# Microcontroller_circuit.net
KiCad netlist of a schematic drawn in Altium Designer
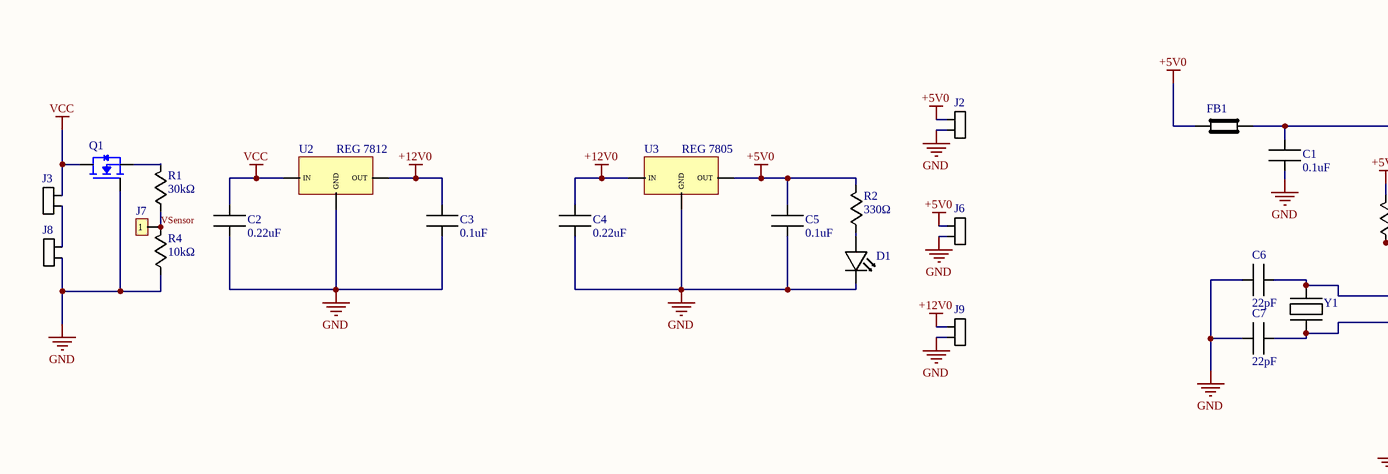
[diagram p0: Microcontroller circuit.SchDoc, left]
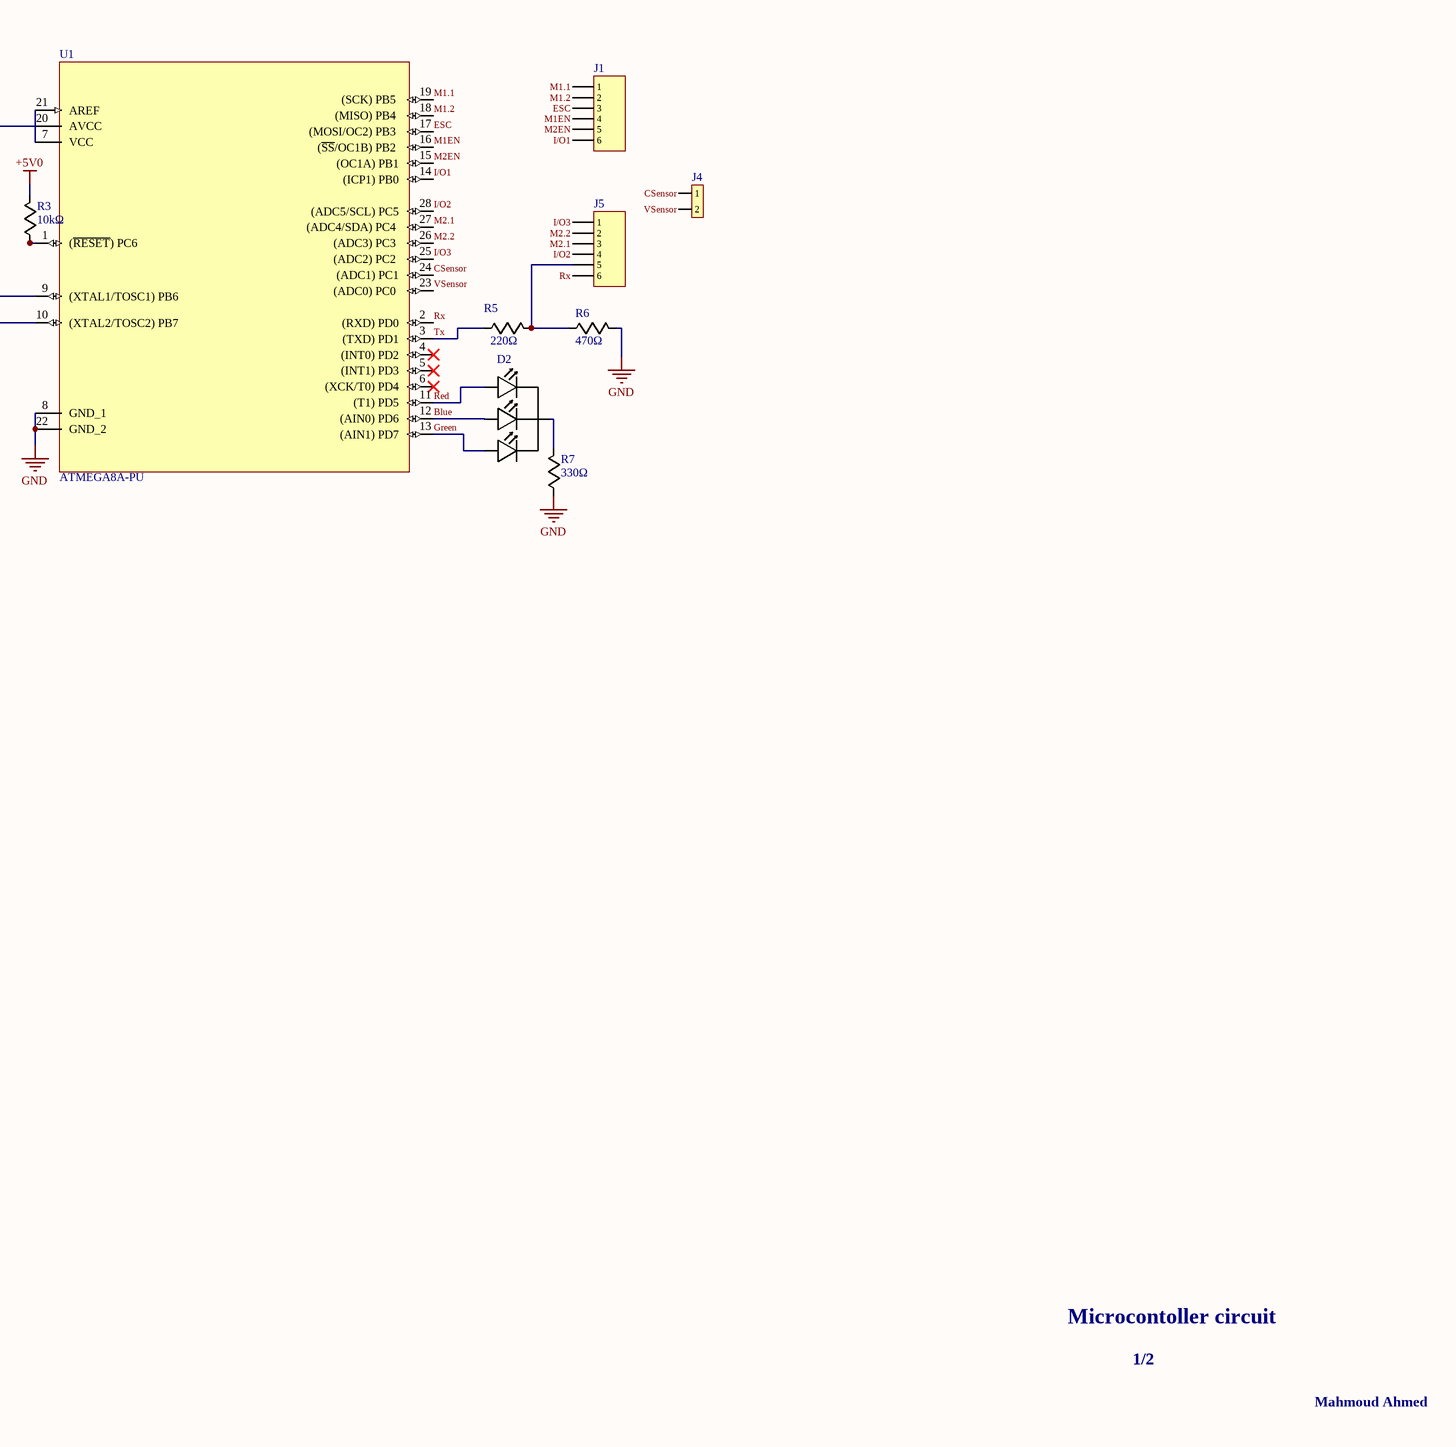
[diagram p1: Microcontroller circuit.SchDoc, right]

(export (version "E")
  (design (tool "Eeschema 10.0.6"))
  (components
    (comp (ref "C1")
      (value "0.1uF")
      (footprint "C0805")
      (description "CAP CER 0.1UF 50V X7R 0805")
      (fields (field (name "MANUFACTURER") "TDK Corporation") (field (name "MPN") "C2012X7R1H104K085AA"))
      (libsource (lib "Microcontroller circuit") (part "0.1uF CAP"))
    )
    (comp (ref "C2")
      (value "0.22uF")
      (footprint "C0805")
      (description "CAP CER 0.22UF 25V X7R 0805")
      (fields (field (name "MPN") "CC0805KRX7R8BB224") (field (name "MANUFACTURER") "YAGEO"))
      (libsource (lib "Microcontroller circuit") (part "0.22uF CAP"))
    )
    (comp (ref "C3")
      (value "0.1uF")
      (footprint "C0805")
      (description "CAP CER 0.1UF 50V X7R 0805")
      (fields (field (name "MANUFACTURER") "TDK Corporation") (field (name "MPN") "C2012X7R1H104K085AA"))
      (libsource (lib "Microcontroller circuit") (part "0.1uF CAP"))
    )
    (comp (ref "C4")
      (value "0.22uF")
      (footprint "C0805")
      (description "CAP CER 0.22UF 25V X7R 0805")
      (fields (field (name "MPN") "CC0805KRX7R8BB224") (field (name "MANUFACTURER") "YAGEO"))
      (libsource (lib "Microcontroller circuit") (part "0.22uF CAP"))
    )
    (comp (ref "C5")
      (value "0.1uF")
      (footprint "C0805")
      (description "CAP CER 0.1UF 50V X7R 0805")
      (fields (field (name "MANUFACTURER") "TDK Corporation") (field (name "MPN") "C2012X7R1H104K085AA"))
      (libsource (lib "Microcontroller circuit") (part "0.1uF CAP"))
    )
    (comp (ref "C6")
      (value "22pF")
      (footprint "C0805")
      (description "CAP THIN FILM 22PF 50V 0805")
      (fields (field (name "MPN") "08055J220FBTTR") (field (name "MANUFACTURER") "KYOCERA AVX"))
      (libsource (lib "Microcontroller circuit") (part "22pF CAP"))
    )
    (comp (ref "C7")
      (value "22pF")
      (footprint "C0805")
      (description "CAP THIN FILM 22PF 50V 0805")
      (fields (field (name "MPN") "08055J220FBTTR") (field (name "MANUFACTURER") "KYOCERA AVX"))
      (libsource (lib "Microcontroller circuit") (part "22pF CAP"))
    )
    (comp (ref "D1")
      (value "RedLED")
      (footprint "THT_LED")
      (description "LED RED CLEAR T-1 T/H")
      (fields (field (name "MPN") "WP132XIT") (field (name "MANUFACTURER") "Kingbright"))
      (libsource (lib "Microcontroller circuit") (part "WP132XIT"))
    )
    (comp (ref "D2")
      (value "WP154A4SUREQBFZGC")
      (footprint "RGB LED")
      (description "LED RGB CLEAR T-1 3/4 T/H")
      (fields (field (name "MANUFACTURER") "Kingbright"))
      (libsource (lib "Microcontroller circuit") (part "RGB LED"))
    )
    (comp (ref "FB1")
      (value "BKP2125HS101-T")
      (footprint "FB0805")
      (description "FERRITE BEAD 100 OHM 0805 1LN")
      (fields (field (name "MANUFACTURER") "Taiyo Yuden"))
      (libsource (lib "Microcontroller circuit") (part "Ferrite Bead"))
    )
    (comp (ref "J1")
      (value "M20-7820646")
      (footprint "HDR 1x6F")
      (description "CONN RCPT 6POS 0.1 TIN PCB")
      (fields (field (name "MANUFACTURER") "Harwin Inc."))
      (libsource (lib "Microcontroller circuit") (part "HDR 1x6F"))
    )
    (comp (ref "J2")
      (value "102-6179-ND")
      (footprint "Terminal block")
      (description "TERMINAL BLOCK, SCREW TYPE, 5.08")
      (fields (field (name "MPN") "TB004-508-02BE") (field (name "MANUFACTURER") "CUI Devices"))
      (libsource (lib "Microcontroller circuit") (part "Terminal block"))
    )
    (comp (ref "J3")
      (value "102-6179-ND")
      (footprint "Terminal block")
      (description "TERMINAL BLOCK, SCREW TYPE, 5.08")
      (fields (field (name "MPN") "TB004-508-02BE") (field (name "MANUFACTURER") "CUI Devices"))
      (libsource (lib "Microcontroller circuit") (part "Terminal block"))
    )
    (comp (ref "J4")
      (value "68000-202HLF")
      (footprint "HDR 1x2M")
      (description "CONN HEADER VERT 2POS 2.54MM")
      (fields (field (name "MANUFACTURER") "Amphenol ICC (FCI)"))
      (libsource (lib "Microcontroller circuit") (part "HDR 1x2M"))
    )
    (comp (ref "J5")
      (value "M20-7820646")
      (footprint "HDR 1x6F")
      (description "CONN RCPT 6POS 0.1 TIN PCB")
      (fields (field (name "MANUFACTURER") "Harwin Inc."))
      (libsource (lib "Microcontroller circuit") (part "HDR 1x6F"))
    )
    (comp (ref "J6")
      (value "102-6179-ND")
      (footprint "Terminal block")
      (description "TERMINAL BLOCK, SCREW TYPE, 5.08")
      (fields (field (name "MPN") "TB004-508-02BE") (field (name "MANUFACTURER") "CUI Devices"))
      (libsource (lib "Microcontroller circuit") (part "Terminal block"))
    )
    (comp (ref "J7")
      (value "PH1-01-UA")
      (footprint "HDR 1x1M")
      (description "CONN HEADER VERT 1POS 2.54MM")
      (fields (field (name "MANUFACTURER") "Adam Tech"))
      (libsource (lib "Microcontroller circuit") (part "HDR 1x1M"))
    )
    (comp (ref "J8")
      (value "102-6179-ND")
      (footprint "Terminal block")
      (description "TERMINAL BLOCK, SCREW TYPE, 5.08")
      (fields (field (name "MPN") "TB004-508-02BE") (field (name "MANUFACTURER") "CUI Devices"))
      (libsource (lib "Microcontroller circuit") (part "Terminal block"))
    )
    (comp (ref "J9")
      (value "102-6179-ND")
      (footprint "Terminal block")
      (description "TERMINAL BLOCK, SCREW TYPE, 5.08")
      (fields (field (name "MPN") "TB004-508-02BE") (field (name "MANUFACTURER") "CUI Devices"))
      (libsource (lib "Microcontroller circuit") (part "Terminal block"))
    )
    (comp (ref "Q1")
      (value "IRF9530NPBF")
      (footprint "IRF9530NPBF")
      (description "MOSFET P-CH 100V 14A TO220AB")
      (fields (field (name "MANUFACTURER") "Infineon Technologies"))
      (libsource (lib "Microcontroller circuit") (part "IRF9530NPBF"))
    )
    (comp (ref "R1")
      (value "30kΩ")
      (footprint "R0805")
      (description "RES 330 OHM 1% 1/8W 0805")
      (fields (field (name "MPN") "RC0805FR-07330RL") (field (name "MANUFACTURER") "YAGEO"))
      (libsource (lib "Microcontroller circuit") (part "330Ω RES"))
    )
    (comp (ref "R2")
      (value "330Ω")
      (footprint "R0805")
      (description "RES 330 OHM 1% 1/8W 0805")
      (fields (field (name "MPN") "RC0805FR-07330RL") (field (name "MANUFACTURER") "YAGEO"))
      (libsource (lib "") (part "330Ω RES_2"))
    )
    (comp (ref "R3")
      (value "10kΩ")
      (footprint "R1206")
      (description "RES 10K OHM 1% 1/4W 1206")
      (fields (field (name "MPN") "RC1206FR-0710KL") (field (name "MANUFACTURER") "YAGEO"))
      (libsource (lib "Microcontroller circuit") (part "10kΩ RES"))
    )
    (comp (ref "R4")
      (value "10kΩ")
      (footprint "R1206")
      (description "RES 10K OHM 1% 1/4W 1206")
      (fields (field (name "MPN") "RC1206FR-0710KL") (field (name "MANUFACTURER") "YAGEO"))
      (libsource (lib "") (part "10kΩ RES_1"))
    )
    (comp (ref "R5")
      (value "220Ω")
      (footprint "R0805")
      (description "RES 330 OHM 1% 1/8W 0805")
      (fields (field (name "MPN") "RC0805FR-07330RL") (field (name "MANUFACTURER") "YAGEO"))
      (libsource (lib "") (part "330Ω RES_1"))
    )
    (comp (ref "R6")
      (value "470Ω")
      (footprint "R0805")
      (description "RES 330 OHM 1% 1/8W 0805")
      (fields (field (name "MPN") "RC0805FR-07330RL") (field (name "MANUFACTURER") "YAGEO"))
      (libsource (lib "") (part "330Ω RES_1"))
    )
    (comp (ref "R7")
      (value "330Ω")
      (footprint "R0805")
      (description "RES 330 OHM 1% 1/8W 0805")
      (fields (field (name "MPN") "RC0805FR-07330RL") (field (name "MANUFACTURER") "YAGEO"))
      (libsource (lib "Microcontroller circuit") (part "330Ω RES"))
    )
    (comp (ref "U1")
      (value "ATMEGA8A-PU")
      (footprint "ATmega8A")
      (description "IC MCU 8BIT 8KB FLASH 28DIP")
      (fields (field (name "MANUFACTURER") "Microchip Technology"))
      (libsource (lib "Microcontroller circuit") (part "ATmega8"))
    )
    (comp (ref "U2")
      (value "REG 7812")
      (footprint "REG 78xx")
      (description "IC REG LINEAR 12V 1A TO220-3")
      (fields (field (name "MPN") "LM7812CT/NOPB") (field (name "MANUFACTURER") "Texas Instruments"))
      (libsource (lib "Microcontroller circuit") (part "LM7812CT/NOPB"))
    )
    (comp (ref "U3")
      (value "REG 7805")
      (footprint "REG 78xx")
      (description "IC REG LINEAR 5V 1A TO220-3")
      (fields (field (name "MPN") "LM7805CT/NOPB") (field (name "MANUFACTURER") "Texas Instruments"))
      (libsource (lib "Microcontroller circuit") (part "LM7805CT/NOPB"))
    )
    (comp (ref "Y1")
      (value "ECS-040-20-4X-DU")
      (footprint "Crystal")
      (description "CRYSTAL 4.0000MHZ 20PF TH")
      (fields (field (name "MANUFACTURER") "ECS Inc."))
      (libsource (lib "Microcontroller circuit") (part "Crystal 4MHz"))
    )
  )
  (nets
    (net (code "1") (name "+5V0") (class "Default")
      (node (ref "C5") (pin "2") (pinfunction "2_2") (pintype "passive"))
      (node (ref "FB1") (pin "2") (pinfunction "2_2") (pintype "passive"))
      (node (ref "J2") (pin "1") (pinfunction "*_1") (pintype "passive"))
      (node (ref "J6") (pin "1") (pinfunction "*_1") (pintype "passive"))
      (node (ref "R2") (pin "2") (pinfunction "*_2") (pintype "passive"))
      (node (ref "R3") (pin "2") (pinfunction "*_2") (pintype "passive"))
      (node (ref "U3") (pin "3") (pinfunction "OUT_3") (pintype "passive"))
    )
    (net (code "2") (name "+12V0") (class "Default")
      (node (ref "C3") (pin "2") (pinfunction "2_2") (pintype "passive"))
      (node (ref "C4") (pin "1") (pinfunction "1_1") (pintype "passive"))
      (node (ref "J9") (pin "1") (pinfunction "*_1") (pintype "passive"))
      (node (ref "U2") (pin "3") (pinfunction "OUT_3") (pintype "passive"))
      (node (ref "U3") (pin "1") (pinfunction "IN_1") (pintype "passive"))
    )
    (net (code "3") (name "/Blue") (class "Default")
      (node (ref "D2") (pin "3") (pinfunction "Blue_3") (pintype "passive"))
      (node (ref "U1") (pin "12") (pinfunction "(AIN0)_PD6_12") (pintype "bidirectional"))
    )
    (net (code "4") (name "/CSensor") (class "Default")
      (node (ref "J4") (pin "1") (pinfunction "1_1") (pintype "passive"))
      (node (ref "U1") (pin "24") (pinfunction "(ADC1)_PC1_24") (pintype "bidirectional"))
    )
    (net (code "5") (name "/ESC") (class "Default")
      (node (ref "J1") (pin "3") (pinfunction "3_3") (pintype "passive"))
      (node (ref "U1") (pin "17") (pinfunction "(MOSI/OC2)_PB3_17") (pintype "bidirectional"))
    )
    (net (code "6") (name "/Green") (class "Default")
      (node (ref "D2") (pin "4") (pinfunction "Green_4") (pintype "passive"))
      (node (ref "U1") (pin "13") (pinfunction "(AIN1)_PD7_13") (pintype "bidirectional"))
    )
    (net (code "7") (name "/I{slash}O1") (class "Default")
      (node (ref "J1") (pin "6") (pinfunction "6_6") (pintype "passive"))
      (node (ref "U1") (pin "14") (pinfunction "(ICP1)_PB0_14") (pintype "bidirectional"))
    )
    (net (code "8") (name "/I{slash}O2") (class "Default")
      (node (ref "J5") (pin "4") (pinfunction "4_4") (pintype "passive"))
      (node (ref "U1") (pin "28") (pinfunction "(ADC5/SCL)_PC5_28") (pintype "bidirectional"))
    )
    (net (code "9") (name "/I{slash}O3") (class "Default")
      (node (ref "J5") (pin "1") (pinfunction "1_1") (pintype "passive"))
      (node (ref "U1") (pin "25") (pinfunction "(ADC2)_PC2_25") (pintype "bidirectional"))
    )
    (net (code "10") (name "/M1.1") (class "Default")
      (node (ref "J1") (pin "1") (pinfunction "1_1") (pintype "passive"))
      (node (ref "U1") (pin "19") (pinfunction "(SCK)_PB5_19") (pintype "bidirectional"))
    )
    (net (code "11") (name "/M1.2") (class "Default")
      (node (ref "J1") (pin "2") (pinfunction "2_2") (pintype "passive"))
      (node (ref "U1") (pin "18") (pinfunction "(MISO)_PB4_18") (pintype "bidirectional"))
    )
    (net (code "12") (name "/M1EN") (class "Default")
      (node (ref "J1") (pin "4") (pinfunction "4_4") (pintype "passive"))
      (node (ref "U1") (pin "16") (pinfunction "(~{SS}/OC1B)_PB2_16") (pintype "bidirectional"))
    )
    (net (code "13") (name "/M2.1") (class "Default")
      (node (ref "J5") (pin "3") (pinfunction "3_3") (pintype "passive"))
      (node (ref "U1") (pin "27") (pinfunction "(ADC4/SDA)_PC4_27") (pintype "bidirectional"))
    )
    (net (code "14") (name "/M2.2") (class "Default")
      (node (ref "J5") (pin "2") (pinfunction "2_2") (pintype "passive"))
      (node (ref "U1") (pin "26") (pinfunction "(ADC3)_PC3_26") (pintype "bidirectional"))
    )
    (net (code "15") (name "/M2EN") (class "Default")
      (node (ref "J1") (pin "5") (pinfunction "5_5") (pintype "passive"))
      (node (ref "U1") (pin "15") (pinfunction "(OC1A)_PB1_15") (pintype "bidirectional"))
    )
    (net (code "16") (name "/Red") (class "Default")
      (node (ref "D2") (pin "1") (pinfunction "Red_1") (pintype "passive"))
      (node (ref "U1") (pin "11") (pinfunction "(T1)_PD5_11") (pintype "bidirectional"))
    )
    (net (code "17") (name "/Rx") (class "Default")
      (node (ref "J5") (pin "6") (pinfunction "6_6") (pintype "passive"))
      (node (ref "U1") (pin "2") (pinfunction "(RXD)_PD0_2") (pintype "bidirectional"))
    )
    (net (code "18") (name "/Tx") (class "Default")
      (node (ref "R5") (pin "1") (pinfunction "*_1") (pintype "passive"))
      (node (ref "U1") (pin "3") (pinfunction "(TXD)_PD1_3") (pintype "bidirectional"))
    )
    (net (code "19") (name "/VSensor") (class "Default")
      (node (ref "J4") (pin "2") (pinfunction "2_2") (pintype "passive"))
      (node (ref "J7") (pin "1") (pinfunction "1_1") (pintype "passive"))
      (node (ref "R1") (pin "1") (pinfunction "*_1") (pintype "passive"))
      (node (ref "R4") (pin "2") (pinfunction "*_2") (pintype "passive"))
      (node (ref "U1") (pin "23") (pinfunction "(ADC0)_PC0_23") (pintype "bidirectional"))
    )
    (net (code "20") (name "GND") (class "Default")
      (node (ref "C1") (pin "1") (pinfunction "1_1") (pintype "passive"))
      (node (ref "C2") (pin "2") (pinfunction "2_2") (pintype "passive"))
      (node (ref "C3") (pin "1") (pinfunction "1_1") (pintype "passive"))
      (node (ref "C4") (pin "2") (pinfunction "2_2") (pintype "passive"))
      (node (ref "C5") (pin "1") (pinfunction "1_1") (pintype "passive"))
      (node (ref "C6") (pin "1") (pinfunction "1_1") (pintype "passive"))
      (node (ref "C7") (pin "1") (pinfunction "1_1") (pintype "passive"))
      (node (ref "D1") (pin "1") (pinfunction "cathode_1") (pintype "passive"))
      (node (ref "J2") (pin "2") (pinfunction "*_2") (pintype "passive"))
      (node (ref "J6") (pin "2") (pinfunction "*_2") (pintype "passive"))
      (node (ref "J8") (pin "1") (pinfunction "*_1") (pintype "passive"))
      (node (ref "J9") (pin "2") (pinfunction "*_2") (pintype "passive"))
      (node (ref "Q1") (pin "1") (pinfunction "G_1") (pintype "passive"))
      (node (ref "R4") (pin "1") (pinfunction "*_1") (pintype "passive"))
      (node (ref "R6") (pin "2") (pinfunction "*_2") (pintype "passive"))
      (node (ref "R7") (pin "1") (pinfunction "*_1") (pintype "passive"))
      (node (ref "U1") (pin "22") (pinfunction "GND_2_22") (pintype "power_in"))
      (node (ref "U1") (pin "8") (pinfunction "GND_1_8") (pintype "power_in"))
      (node (ref "U2") (pin "2") (pinfunction "GND_2") (pintype "passive"))
      (node (ref "U3") (pin "2") (pinfunction "GND_2") (pintype "passive"))
    )
    (net (code "21") (name "Net-(D1-Anode)") (class "Default")
      (node (ref "D1") (pin "2") (pinfunction "Anode_2") (pintype "passive"))
      (node (ref "R2") (pin "1") (pinfunction "*_1") (pintype "passive"))
    )
    (net (code "22") (name "Net-(D2-Common_Cathode)") (class "Default")
      (node (ref "D2") (pin "2") (pinfunction "Common_Cathode_2") (pintype "passive"))
      (node (ref "R7") (pin "2") (pinfunction "*_2") (pintype "passive"))
    )
    (net (code "23") (name "Net-(J3-*-Pad2)") (class "Default")
      (node (ref "J3") (pin "2") (pinfunction "*_2") (pintype "passive"))
      (node (ref "J8") (pin "2") (pinfunction "*_2") (pintype "passive"))
    )
    (net (code "24") (name "Net-(J5-Pad5)") (class "Default")
      (node (ref "J5") (pin "5") (pinfunction "5_5") (pintype "passive"))
      (node (ref "R5") (pin "2") (pinfunction "*_2") (pintype "passive"))
      (node (ref "R6") (pin "1") (pinfunction "*_1") (pintype "passive"))
    )
    (net (code "25") (name "Net-(Q1-S)") (class "Default")
      (node (ref "Q1") (pin "3") (pinfunction "S_3") (pintype "passive"))
      (node (ref "R1") (pin "2") (pinfunction "*_2") (pintype "passive"))
    )
    (net (code "26") (name "Net-(U1-(XTAL1{slash}TOSC1)_PB6)") (class "Default")
      (node (ref "C6") (pin "2") (pinfunction "2_2") (pintype "passive"))
      (node (ref "U1") (pin "9") (pinfunction "(XTAL1/TOSC1)_PB6_9") (pintype "bidirectional"))
      (node (ref "Y1") (pin "2") (pinfunction "2_2") (pintype "passive"))
    )
    (net (code "27") (name "Net-(U1-(XTAL2{slash}TOSC2)_PB7)") (class "Default")
      (node (ref "C7") (pin "2") (pinfunction "2_2") (pintype "passive"))
      (node (ref "U1") (pin "10") (pinfunction "(XTAL2/TOSC2)_PB7_10") (pintype "bidirectional"))
      (node (ref "Y1") (pin "1") (pinfunction "1_1") (pintype "passive"))
    )
    (net (code "28") (name "Net-(U1-(~{RESET})_PC6)") (class "Default")
      (node (ref "R3") (pin "1") (pinfunction "*_1") (pintype "passive"))
      (node (ref "U1") (pin "1") (pinfunction "(~{RESET})_PC6_1") (pintype "bidirectional"))
    )
    (net (code "29") (name "Net-(U1-AREF)") (class "Default")
      (node (ref "C1") (pin "2") (pinfunction "2_2") (pintype "passive"))
      (node (ref "FB1") (pin "1") (pinfunction "1_1") (pintype "passive"))
      (node (ref "U1") (pin "20") (pinfunction "AVCC_20") (pintype "power_in"))
      (node (ref "U1") (pin "21") (pinfunction "AREF_21") (pintype "input"))
      (node (ref "U1") (pin "7") (pinfunction "VCC_7") (pintype "power_in"))
    )
    (net (code "30") (name "VCC") (class "Default")
      (node (ref "C2") (pin "1") (pinfunction "1_1") (pintype "passive"))
      (node (ref "J3") (pin "1") (pinfunction "*_1") (pintype "passive"))
      (node (ref "Q1") (pin "2") (pinfunction "D_2") (pintype "passive"))
      (node (ref "U2") (pin "1") (pinfunction "IN_1") (pintype "passive"))
    )
    (net (code "31") (name "unconnected-(U1-(INT0)_PD2-Pad4)") (class "Default")
      (node (ref "U1") (pin "4") (pinfunction "(INT0)_PD2_4") (pintype "bidirectional+no_connect"))
    )
    (net (code "32") (name "unconnected-(U1-(INT1)_PD3-Pad5)") (class "Default")
      (node (ref "U1") (pin "5") (pinfunction "(INT1)_PD3_5") (pintype "bidirectional+no_connect"))
    )
    (net (code "33") (name "unconnected-(U1-(XCK{slash}T0)_PD4-Pad6)") (class "Default")
      (node (ref "U1") (pin "6") (pinfunction "(XCK/T0)_PD4_6") (pintype "bidirectional+no_connect"))
    )
  )
)
